# Controller_Board_Interface.net
KiCad netlist of a schematic drawn in Altium Designer
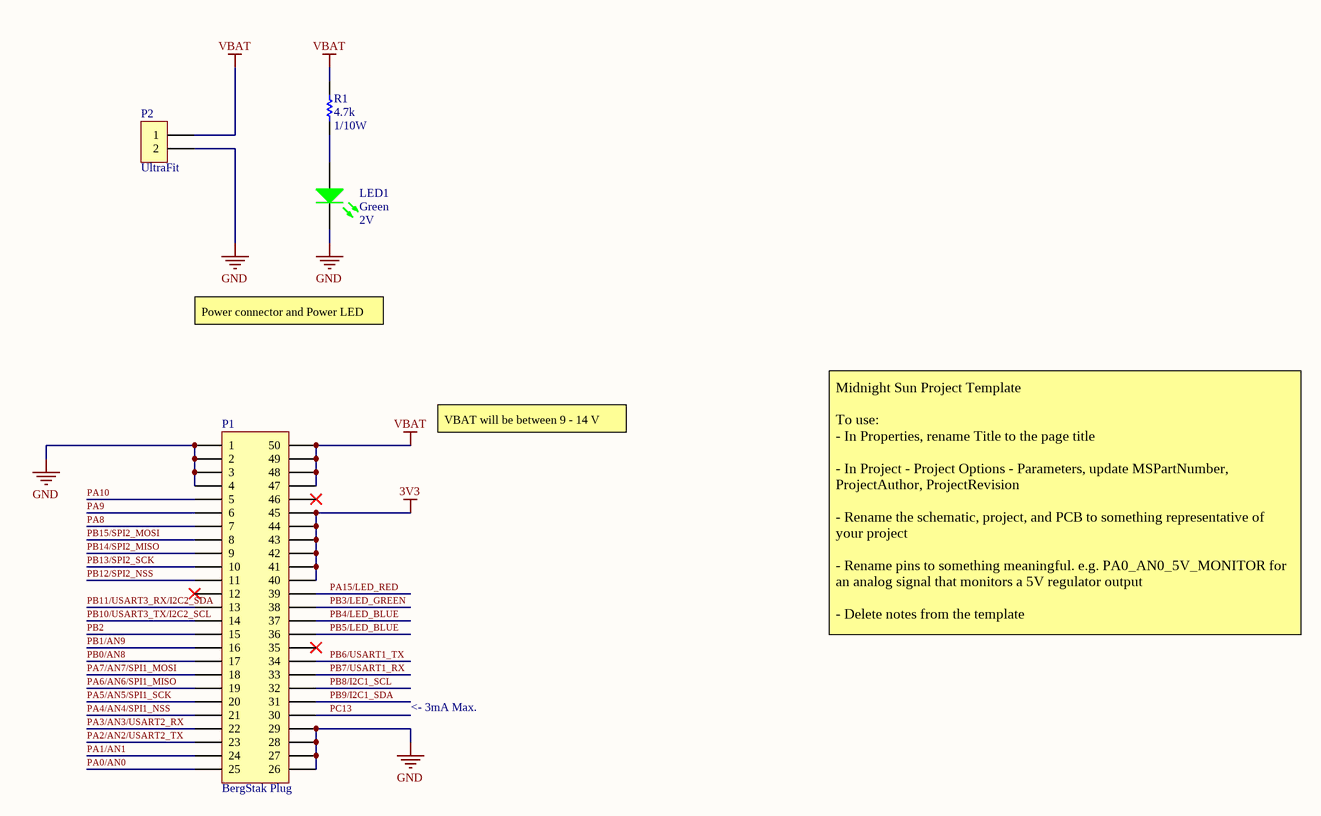
[diagram p0: Controller_Board_Interface.SchDoc]

(export (version "E")
  (design (tool "Eeschema 10.0.6"))
  (components
    (comp (ref "LED1")
      (value "LED GREEN CLEAR 2V 0603")
      (footprint "LED_0603")
      (description "Green 572nm LED Indication - Discrete 2V 0603 (1608 Metric)")
      (fields
        (field (name "MANUFACTURER") "Wurth Electronics Inc.")
        (field (name "MANUFACTURER PART NUMBER") "150060VS75000")
        (field (name "COLOR") "Green")
        (field (name "VOLTAGE - FORWARD (VF) (TYP)") "2V")
      )
      (libsource (lib "Schematic Diagrams") (part "LED GREEN CLEAR 2V 0603"))
    )
    (comp (ref "P1")
      (value "CONN 50POS Bergstak Plug 0.02\"")
      (footprint "CONN, Bergstak 50 Pos Plug")
      (description "50 Position Connector Plug, Outer Shroud Contacts Surface Mount Gold")
      (fields (field (name "SERIES") "BergStak Plug"))
      (libsource (lib "Schematic Diagrams") (part "CONN 50POS Bergstak Plug 0.02{dblquote}"))
    )
    (comp (ref "P2")
      (value "CONN 2POS ULTRA-FIT 0.138\"")
      (footprint "CONN, 2POS ULTRA-FIT")
      (description "Connector Header Through Hole 2 position 0.138\" (3.50mm)")
      (fields
        (field (name "MANUFACTURER") "Molex")
        (field (name "MANUFACTURER PART NUMBER") "1722871102")
        (field (name "SERIES") "UltraFit")
      )
      (libsource (lib "Schematic Diagrams") (part "CONN 2POS ULTRA-FIT 0.138{dblquote}"))
    )
    (comp (ref "R1")
      (value "RES 4.7K OHM 1% 1/10W 0603")
      (footprint "RES, 0603")
      (description "4.7k Ohm ±1% 0.1W, 1/10W Chip Resistor 0603 (1608 Metric) Moisture Resistant Thick Film")
      (fields
        (field (name "TOLERANCE") "±1%")
        (field (name "RESISTANCE (OHMS)") "4.7k")
        (field (name "POWER (WATTS)") "1/10W")
      )
      (libsource (lib "Schematic Diagrams") (part "RES 4.7K OHM 1% 1/10W 0603"))
    )
  )
  (nets
    (net (code "1") (name "/PA0{slash}AN0") (class "Default")
      (node (ref "P1") (pin "25") (pinfunction "25_25") (pintype "passive"))
    )
    (net (code "2") (name "/PA1{slash}AN1") (class "Default")
      (node (ref "P1") (pin "24") (pinfunction "24_24") (pintype "passive"))
    )
    (net (code "3") (name "/PA2{slash}AN2{slash}USART2_TX") (class "Default")
      (node (ref "P1") (pin "23") (pinfunction "23_23") (pintype "passive"))
    )
    (net (code "4") (name "/PA3{slash}AN3{slash}USART2_RX") (class "Default")
      (node (ref "P1") (pin "22") (pinfunction "22_22") (pintype "passive"))
    )
    (net (code "5") (name "/PA4{slash}AN4{slash}SPI1_NSS") (class "Default")
      (node (ref "P1") (pin "21") (pinfunction "21_21") (pintype "passive"))
    )
    (net (code "6") (name "/PA5{slash}AN5{slash}SPI1_SCK") (class "Default")
      (node (ref "P1") (pin "20") (pinfunction "20_20") (pintype "passive"))
    )
    (net (code "7") (name "/PA6{slash}AN6{slash}SPI1_MISO") (class "Default")
      (node (ref "P1") (pin "19") (pinfunction "19_19") (pintype "passive"))
    )
    (net (code "8") (name "/PA7{slash}AN7{slash}SPI1_MOSI") (class "Default")
      (node (ref "P1") (pin "18") (pinfunction "18_18") (pintype "passive"))
    )
    (net (code "9") (name "/PA8") (class "Default")
      (node (ref "P1") (pin "7") (pinfunction "7_7") (pintype "passive"))
    )
    (net (code "10") (name "/PA9") (class "Default")
      (node (ref "P1") (pin "6") (pinfunction "6_6") (pintype "passive"))
    )
    (net (code "11") (name "/PA10") (class "Default")
      (node (ref "P1") (pin "5") (pinfunction "5_5") (pintype "passive"))
    )
    (net (code "12") (name "/PA15{slash}LED_RED") (class "Default")
      (node (ref "P1") (pin "39") (pinfunction "39_39") (pintype "passive"))
    )
    (net (code "13") (name "/PB0{slash}AN8") (class "Default")
      (node (ref "P1") (pin "17") (pinfunction "17_17") (pintype "passive"))
    )
    (net (code "14") (name "/PB1{slash}AN9") (class "Default")
      (node (ref "P1") (pin "16") (pinfunction "16_16") (pintype "passive"))
    )
    (net (code "15") (name "/PB2") (class "Default")
      (node (ref "P1") (pin "15") (pinfunction "15_15") (pintype "passive"))
    )
    (net (code "16") (name "/PB3{slash}LED_GREEN") (class "Default")
      (node (ref "P1") (pin "38") (pinfunction "38_38") (pintype "passive"))
    )
    (net (code "17") (name "/PB4{slash}LED_BLUE") (class "Default")
      (node (ref "P1") (pin "37") (pinfunction "37_37") (pintype "passive"))
    )
    (net (code "18") (name "/PB5{slash}LED_BLUE") (class "Default")
      (node (ref "P1") (pin "36") (pinfunction "36_36") (pintype "passive"))
    )
    (net (code "19") (name "/PB6{slash}USART1_TX") (class "Default")
      (node (ref "P1") (pin "34") (pinfunction "34_34") (pintype "passive"))
    )
    (net (code "20") (name "/PB7{slash}USART1_RX") (class "Default")
      (node (ref "P1") (pin "33") (pinfunction "33_33") (pintype "passive"))
    )
    (net (code "21") (name "/PB8{slash}I2C1_SCL") (class "Default")
      (node (ref "P1") (pin "32") (pinfunction "32_32") (pintype "passive"))
    )
    (net (code "22") (name "/PB9{slash}I2C1_SDA") (class "Default")
      (node (ref "P1") (pin "31") (pinfunction "31_31") (pintype "passive"))
    )
    (net (code "23") (name "/PB10{slash}USART3_TX{slash}I2C2_SCL") (class "Default")
      (node (ref "P1") (pin "14") (pinfunction "14_14") (pintype "passive"))
    )
    (net (code "24") (name "/PB11{slash}USART3_RX{slash}I2C2_SDA") (class "Default")
      (node (ref "P1") (pin "13") (pinfunction "13_13") (pintype "passive"))
    )
    (net (code "25") (name "/PB12{slash}SPI2_NSS") (class "Default")
      (node (ref "P1") (pin "11") (pinfunction "11_11") (pintype "passive"))
    )
    (net (code "26") (name "/PB13{slash}SPI2_SCK") (class "Default")
      (node (ref "P1") (pin "10") (pinfunction "10_10") (pintype "passive"))
    )
    (net (code "27") (name "/PB14{slash}SPI2_MISO") (class "Default")
      (node (ref "P1") (pin "9") (pinfunction "9_9") (pintype "passive"))
    )
    (net (code "28") (name "/PB15{slash}SPI2_MOSI") (class "Default")
      (node (ref "P1") (pin "8") (pinfunction "8_8") (pintype "passive"))
    )
    (net (code "29") (name "/PC13") (class "Default")
      (node (ref "P1") (pin "30") (pinfunction "30_30") (pintype "passive"))
    )
    (net (code "30") (name "3V3") (class "Default")
      (node (ref "P1") (pin "40") (pinfunction "40_40") (pintype "passive"))
      (node (ref "P1") (pin "41") (pinfunction "41_41") (pintype "passive"))
      (node (ref "P1") (pin "42") (pinfunction "42_42") (pintype "passive"))
      (node (ref "P1") (pin "43") (pinfunction "43_43") (pintype "passive"))
      (node (ref "P1") (pin "44") (pinfunction "44_44") (pintype "passive"))
      (node (ref "P1") (pin "45") (pinfunction "45_45") (pintype "passive"))
    )
    (net (code "31") (name "GND") (class "Default")
      (node (ref "LED1") (pin "2") (pinfunction "K_2") (pintype "passive"))
      (node (ref "P1") (pin "1") (pinfunction "1_1") (pintype "passive"))
      (node (ref "P1") (pin "2") (pinfunction "2_2") (pintype "passive"))
      (node (ref "P1") (pin "26") (pinfunction "26_26") (pintype "passive"))
      (node (ref "P1") (pin "27") (pinfunction "27_27") (pintype "passive"))
      (node (ref "P1") (pin "28") (pinfunction "28_28") (pintype "passive"))
      (node (ref "P1") (pin "29") (pinfunction "29_29") (pintype "passive"))
      (node (ref "P1") (pin "3") (pinfunction "3_3") (pintype "passive"))
      (node (ref "P1") (pin "4") (pinfunction "4_4") (pintype "passive"))
      (node (ref "P2") (pin "2") (pinfunction "2_2") (pintype "passive"))
    )
    (net (code "32") (name "Net-(LED1-A)") (class "Default")
      (node (ref "LED1") (pin "1") (pinfunction "A_1") (pintype "passive"))
      (node (ref "R1") (pin "2") (pinfunction "2_2") (pintype "passive"))
    )
    (net (code "33") (name "VBAT") (class "Default")
      (node (ref "P1") (pin "47") (pinfunction "47_47") (pintype "passive"))
      (node (ref "P1") (pin "48") (pinfunction "48_48") (pintype "passive"))
      (node (ref "P1") (pin "49") (pinfunction "49_49") (pintype "passive"))
      (node (ref "P1") (pin "50") (pinfunction "50_50") (pintype "passive"))
      (node (ref "P2") (pin "1") (pinfunction "1_1") (pintype "passive"))
      (node (ref "R1") (pin "1") (pinfunction "1_1") (pintype "passive"))
    )
    (net (code "34") (name "unconnected-(P1-Pad12)") (class "Default")
      (node (ref "P1") (pin "12") (pinfunction "12_12") (pintype "passive+no_connect"))
    )
    (net (code "35") (name "unconnected-(P1-Pad35)") (class "Default")
      (node (ref "P1") (pin "35") (pinfunction "35_35") (pintype "passive+no_connect"))
    )
    (net (code "36") (name "unconnected-(P1-Pad46)") (class "Default")
      (node (ref "P1") (pin "46") (pinfunction "46_46") (pintype "passive+no_connect"))
    )
  )
)
